# esp32-mementoV3-2021.net
KiCad netlist of a schematic drawn in EAGLE
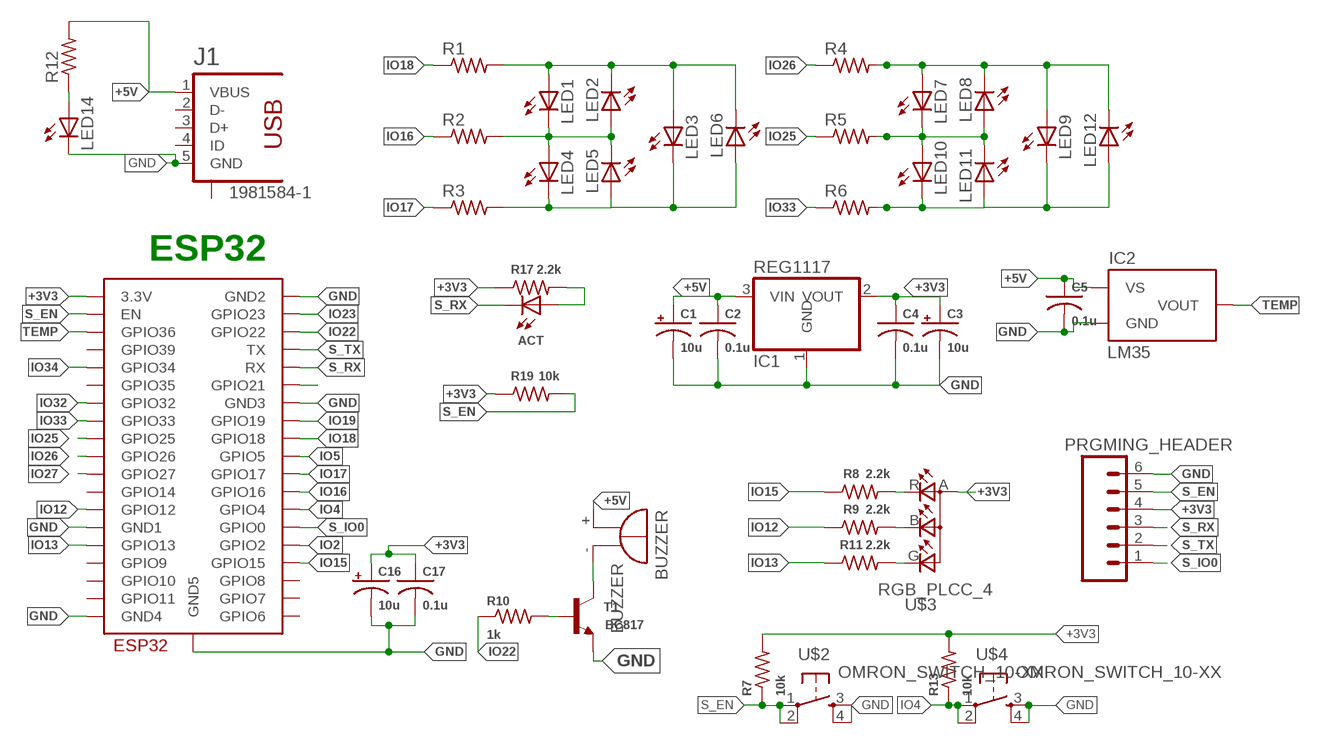
[diagram p0: schematic, sheet 1]

(export (version "E")
  (design (tool "Eeschema 10.0.6"))
  (components
    (comp (ref "ACT")
      (value "LEDCHIPLED_1206")
      (footprint "eagle-import:CHIPLED_1206")
      (libsource (lib "eagle-import") (part "LEDCHIPLED_1206"))
    )
    (comp (ref "BUZZER")
      (value "BUZZER")
      (footprint "eagle-import:F_TMB")
      (libsource (lib "eagle-import") (part "BUZZER"))
    )
    (comp (ref "C1")
      (value "10u")
      (footprint "eagle-import:B_3528-21R")
      (libsource (lib "eagle-import") (part "CAP_POL_16V"))
    )
    (comp (ref "C2")
      (value "0.1u")
      (footprint "eagle-import:C0603")
      (libsource (lib "eagle-import") (part "CAP0603"))
    )
    (comp (ref "C3")
      (value "10u")
      (footprint "eagle-import:B_3528-21R")
      (libsource (lib "eagle-import") (part "CAP_POL_16V"))
    )
    (comp (ref "C4")
      (value "0.1u")
      (footprint "eagle-import:C0603")
      (libsource (lib "eagle-import") (part "CAP0603"))
    )
    (comp (ref "C5")
      (value "0.1u")
      (footprint "eagle-import:C0603")
      (libsource (lib "eagle-import") (part "CAP0603"))
    )
    (comp (ref "C16")
      (value "10u")
      (footprint "eagle-import:B_3528-21R")
      (libsource (lib "eagle-import") (part "CAP_POL_16V"))
    )
    (comp (ref "C17")
      (value "0.1u")
      (footprint "eagle-import:C0603")
      (libsource (lib "eagle-import") (part "CAP0603"))
    )
    (comp (ref "ESP32_MODULE")
      (value "ESP32-WROOM")
      (footprint "eagle-import:ESP32-WROOM")
      (libsource (lib "eagle-import") (part "ESP32-WROOM"))
    )
    (comp (ref "IC1")
      (value "REG1117")
      (footprint "eagle-import:SOT223")
      (libsource (lib "eagle-import") (part "REG1117"))
    )
    (comp (ref "IC2")
      (value "LM35")
      (footprint "eagle-import:TO92")
      (libsource (lib "eagle-import") (part "LM35"))
    )
    (comp (ref "J1")
      (value "1981584-1")
      (footprint "eagle-import:1981584-1")
      (libsource (lib "eagle-import") (part "1981584-1"))
    )
    (comp (ref "LED1")
      (value "LED1206")
      (footprint "eagle-import:CHIPLED_1206")
      (libsource (lib "eagle-import") (part "LED1206"))
    )
    (comp (ref "LED2")
      (value "LED1206")
      (footprint "eagle-import:CHIPLED_1206")
      (libsource (lib "eagle-import") (part "LED1206"))
    )
    (comp (ref "LED3")
      (value "LED1206")
      (footprint "eagle-import:CHIPLED_1206")
      (libsource (lib "eagle-import") (part "LED1206"))
    )
    (comp (ref "LED4")
      (value "LED1206")
      (footprint "eagle-import:CHIPLED_1206")
      (libsource (lib "eagle-import") (part "LED1206"))
    )
    (comp (ref "LED5")
      (value "LED1206")
      (footprint "eagle-import:CHIPLED_1206")
      (libsource (lib "eagle-import") (part "LED1206"))
    )
    (comp (ref "LED6")
      (value "LED1206")
      (footprint "eagle-import:CHIPLED_1206")
      (libsource (lib "eagle-import") (part "LED1206"))
    )
    (comp (ref "LED7")
      (value "LED1206")
      (footprint "eagle-import:CHIPLED_1206")
      (libsource (lib "eagle-import") (part "LED1206"))
    )
    (comp (ref "LED8")
      (value "LED1206")
      (footprint "eagle-import:CHIPLED_1206")
      (libsource (lib "eagle-import") (part "LED1206"))
    )
    (comp (ref "LED9")
      (value "LED1206")
      (footprint "eagle-import:CHIPLED_1206")
      (libsource (lib "eagle-import") (part "LED1206"))
    )
    (comp (ref "LED10")
      (value "LED1206")
      (footprint "eagle-import:CHIPLED_1206")
      (libsource (lib "eagle-import") (part "LED1206"))
    )
    (comp (ref "LED11")
      (value "LED1206")
      (footprint "eagle-import:CHIPLED_1206")
      (libsource (lib "eagle-import") (part "LED1206"))
    )
    (comp (ref "LED12")
      (value "LED1206")
      (footprint "eagle-import:CHIPLED_1206")
      (libsource (lib "eagle-import") (part "LED1206"))
    )
    (comp (ref "LED14")
      (value "LED1206")
      (footprint "eagle-import:CHIPLED_1206")
      (libsource (lib "eagle-import") (part "LED1206"))
    )
    (comp (ref "PRGMING_HEADER")
      (value "M06")
      (footprint "eagle-import:06P")
      (libsource (lib "eagle-import") (part "M06"))
    )
    (comp (ref "R1")
      (value "RESISTOR0805")
      (footprint "eagle-import:R0805")
      (libsource (lib "eagle-import") (part "RESISTOR0805"))
    )
    (comp (ref "R2")
      (value "RESISTOR0805")
      (footprint "eagle-import:R0805")
      (libsource (lib "eagle-import") (part "RESISTOR0805"))
    )
    (comp (ref "R3")
      (value "RESISTOR0805")
      (footprint "eagle-import:R0805")
      (libsource (lib "eagle-import") (part "RESISTOR0805"))
    )
    (comp (ref "R4")
      (value "RESISTOR0805")
      (footprint "eagle-import:R0805")
      (libsource (lib "eagle-import") (part "RESISTOR0805"))
    )
    (comp (ref "R5")
      (value "RESISTOR0805")
      (footprint "eagle-import:R0805")
      (libsource (lib "eagle-import") (part "RESISTOR0805"))
    )
    (comp (ref "R6")
      (value "RESISTOR0805")
      (footprint "eagle-import:R0805")
      (libsource (lib "eagle-import") (part "RESISTOR0805"))
    )
    (comp (ref "R7")
      (value "10k")
      (footprint "eagle-import:M0805")
      (libsource (lib "eagle-import") (part "rcl_334_R-US_M0805"))
    )
    (comp (ref "R8")
      (value "2.2k")
      (footprint "eagle-import:R0805")
      (libsource (lib "eagle-import") (part "R-US_R0805"))
    )
    (comp (ref "R9")
      (value "2.2k")
      (footprint "eagle-import:R0805")
      (libsource (lib "eagle-import") (part "R-US_R0805"))
    )
    (comp (ref "R10")
      (value "1k")
      (footprint "eagle-import:M0805")
      (libsource (lib "eagle-import") (part "rcl_334_R-US_M0805"))
    )
    (comp (ref "R11")
      (value "2.2k")
      (footprint "eagle-import:R0805")
      (libsource (lib "eagle-import") (part "R-US_R0805"))
    )
    (comp (ref "R12")
      (value "RESISTOR0805")
      (footprint "eagle-import:R0805")
      (libsource (lib "eagle-import") (part "RESISTOR0805"))
    )
    (comp (ref "R13")
      (value "10k")
      (footprint "eagle-import:M0805")
      (libsource (lib "eagle-import") (part "rcl_334_R-US_M0805"))
    )
    (comp (ref "R17")
      (value "2.2k")
      (footprint "eagle-import:R0805")
      (libsource (lib "eagle-import") (part "R-US_R0805"))
    )
    (comp (ref "R19")
      (value "10k")
      (footprint "eagle-import:R0805")
      (libsource (lib "eagle-import") (part "R-US_R0805"))
    )
    (comp (ref "T1")
      (value "BC817")
      (footprint "eagle-import:SOT23-BEC")
      (libsource (lib "eagle-import") (part "BC817SMD-40"))
    )
    (comp (ref "U$2")
      (value "OMRON_SWITCH_10-XX")
      (footprint "eagle-import:B3F-10XX")
      (libsource (lib "eagle-import") (part "OMRON_SWITCH_10-XX"))
    )
    (comp (ref "U$3")
      (value "RGB_PLCC_4")
      (footprint "eagle-import:PLCC-4")
      (libsource (lib "eagle-import") (part "RGB_PLCC_4"))
    )
    (comp (ref "U$4")
      (value "OMRON_SWITCH_10-XX")
      (footprint "eagle-import:B3F-10XX")
      (libsource (lib "eagle-import") (part "OMRON_SWITCH_10-XX"))
    )
  )
  (nets
    (net (code "1") (name "+3V3") (class "Default")
      (node (ref "C16") (pin "+") (pinfunction "+_+") (pintype "passive"))
      (node (ref "C17") (pin "1") (pinfunction "1_1") (pintype "passive"))
      (node (ref "C3") (pin "+") (pinfunction "+_+") (pintype "passive"))
      (node (ref "C4") (pin "1") (pinfunction "1_1") (pintype "passive"))
      (node (ref "ESP32_MODULE") (pin "3V3") (pinfunction "3.3V_3V3") (pintype "bidirectional"))
      (node (ref "IC1") (pin "2") (pinfunction "VOUT_2") (pintype "output"))
      (node (ref "PRGMING_HEADER") (pin "4") (pinfunction "4_4") (pintype "passive"))
      (node (ref "R13") (pin "2") (pinfunction "2_2") (pintype "passive"))
      (node (ref "R17") (pin "1") (pinfunction "1_1") (pintype "passive"))
      (node (ref "R19") (pin "1") (pinfunction "1_1") (pintype "passive"))
      (node (ref "R7") (pin "2") (pinfunction "2_2") (pintype "passive"))
      (node (ref "U$3") (pin "A") (pinfunction "A2_A") (pintype "passive"))
    )
    (net (code "2") (name "+5V") (class "Default")
      (node (ref "BUZZER") (pin "+") (pinfunction "+_+") (pintype "passive"))
      (node (ref "C1") (pin "+") (pinfunction "+_+") (pintype "passive"))
      (node (ref "C2") (pin "1") (pinfunction "1_1") (pintype "passive"))
      (node (ref "C5") (pin "1") (pinfunction "1_1") (pintype "passive"))
      (node (ref "IC1") (pin "3") (pinfunction "VIN_3") (pintype "input"))
      (node (ref "IC2") (pin "VS") (pinfunction "VS_VS") (pintype "passive"))
      (node (ref "J1") (pin "1") (pinfunction "VBUS_1") (pintype "passive"))
      (node (ref "R12") (pin "2") (pinfunction "2_2") (pintype "passive"))
    )
    (net (code "3") (name "GND") (class "Default")
      (node (ref "C1") (pin "-") (pinfunction "-_-") (pintype "passive"))
      (node (ref "C16") (pin "-") (pinfunction "-_-") (pintype "passive"))
      (node (ref "C17") (pin "2") (pinfunction "2_2") (pintype "passive"))
      (node (ref "C2") (pin "2") (pinfunction "2_2") (pintype "passive"))
      (node (ref "C3") (pin "-") (pinfunction "-_-") (pintype "passive"))
      (node (ref "C4") (pin "2") (pinfunction "2_2") (pintype "passive"))
      (node (ref "C5") (pin "2") (pinfunction "2_2") (pintype "passive"))
      (node (ref "ESP32_MODULE") (pin "GND1") (pinfunction "GND1_GND1") (pintype "bidirectional"))
      (node (ref "ESP32_MODULE") (pin "GND2") (pinfunction "GND2_GND2") (pintype "bidirectional"))
      (node (ref "ESP32_MODULE") (pin "GND3") (pinfunction "GND3_GND3") (pintype "bidirectional"))
      (node (ref "ESP32_MODULE") (pin "GND4") (pinfunction "GND4_GND4") (pintype "bidirectional"))
      (node (ref "ESP32_MODULE") (pin "GND5") (pinfunction "GND5_GND5") (pintype "bidirectional"))
      (node (ref "IC1") (pin "1") (pinfunction "GND_1") (pintype "power_in"))
      (node (ref "IC2") (pin "GND") (pinfunction "GND_GND") (pintype "passive"))
      (node (ref "J1") (pin "5") (pinfunction "GND_5") (pintype "passive"))
      (node (ref "LED14") (pin "C") (pinfunction "C_C") (pintype "passive"))
      (node (ref "PRGMING_HEADER") (pin "6") (pinfunction "6_6") (pintype "passive"))
      (node (ref "T1") (pin "E") (pinfunction "E_E") (pintype "passive"))
      (node (ref "U$2") (pin "3") (pinfunction "S_3") (pintype "passive"))
      (node (ref "U$2") (pin "4") (pinfunction "S1_4") (pintype "passive"))
      (node (ref "U$4") (pin "3") (pinfunction "S_3") (pintype "passive"))
      (node (ref "U$4") (pin "4") (pinfunction "S1_4") (pintype "passive"))
    )
    (net (code "4") (name "IO2") (class "Default")
      (node (ref "ESP32_MODULE") (pin "IO2") (pinfunction "GPIO2_IO2") (pintype "bidirectional"))
    )
    (net (code "5") (name "IO4") (class "Default")
      (node (ref "ESP32_MODULE") (pin "IO4") (pinfunction "GPIO4_IO4") (pintype "bidirectional"))
      (node (ref "R13") (pin "1") (pinfunction "1_1") (pintype "passive"))
      (node (ref "U$4") (pin "1") (pinfunction "P_1") (pintype "passive"))
      (node (ref "U$4") (pin "2") (pinfunction "P1_2") (pintype "passive"))
    )
    (net (code "6") (name "IO5") (class "Default")
      (node (ref "ESP32_MODULE") (pin "IO5") (pinfunction "GPIO5_IO5") (pintype "bidirectional"))
    )
    (net (code "7") (name "IO12") (class "Default")
      (node (ref "ESP32_MODULE") (pin "IO12") (pinfunction "GPIO12_IO12") (pintype "bidirectional"))
      (node (ref "R9") (pin "1") (pinfunction "1_1") (pintype "passive"))
    )
    (net (code "8") (name "IO13") (class "Default")
      (node (ref "ESP32_MODULE") (pin "IO13") (pinfunction "GPIO13_IO13") (pintype "bidirectional"))
      (node (ref "R11") (pin "1") (pinfunction "1_1") (pintype "passive"))
    )
    (net (code "9") (name "IO15") (class "Default")
      (node (ref "ESP32_MODULE") (pin "IO15") (pinfunction "GPIO15_IO15") (pintype "bidirectional"))
      (node (ref "R8") (pin "1") (pinfunction "1_1") (pintype "passive"))
    )
    (net (code "10") (name "IO16") (class "Default")
      (node (ref "ESP32_MODULE") (pin "IO16") (pinfunction "GPIO16_IO16") (pintype "bidirectional"))
      (node (ref "R2") (pin "1") (pinfunction "1_1") (pintype "passive"))
    )
    (net (code "11") (name "IO17") (class "Default")
      (node (ref "ESP32_MODULE") (pin "IO17") (pinfunction "GPIO17_IO17") (pintype "bidirectional"))
      (node (ref "R3") (pin "1") (pinfunction "1_1") (pintype "passive"))
    )
    (net (code "12") (name "IO18") (class "Default")
      (node (ref "ESP32_MODULE") (pin "IO18") (pinfunction "GPIO18_IO18") (pintype "bidirectional"))
      (node (ref "R1") (pin "1") (pinfunction "1_1") (pintype "passive"))
    )
    (net (code "13") (name "IO19") (class "Default")
      (node (ref "ESP32_MODULE") (pin "IO19") (pinfunction "GPIO19_IO19") (pintype "bidirectional"))
    )
    (net (code "14") (name "IO22") (class "Default")
      (node (ref "ESP32_MODULE") (pin "IO22") (pinfunction "GPIO22_IO22") (pintype "bidirectional"))
      (node (ref "R10") (pin "1") (pinfunction "1_1") (pintype "passive"))
    )
    (net (code "15") (name "IO23") (class "Default")
      (node (ref "ESP32_MODULE") (pin "IO23") (pinfunction "GPIO23_IO23") (pintype "bidirectional"))
    )
    (net (code "16") (name "IO25") (class "Default")
      (node (ref "ESP32_MODULE") (pin "IO25") (pinfunction "GPIO25_IO25") (pintype "bidirectional"))
      (node (ref "R5") (pin "1") (pinfunction "1_1") (pintype "passive"))
    )
    (net (code "17") (name "IO26") (class "Default")
      (node (ref "ESP32_MODULE") (pin "IO26") (pinfunction "GPIO26_IO26") (pintype "bidirectional"))
      (node (ref "R4") (pin "1") (pinfunction "1_1") (pintype "passive"))
    )
    (net (code "18") (name "IO27") (class "Default")
      (node (ref "ESP32_MODULE") (pin "IO27") (pinfunction "GPIO27_IO27") (pintype "bidirectional"))
    )
    (net (code "19") (name "IO32") (class "Default")
      (node (ref "ESP32_MODULE") (pin "IO32") (pinfunction "GPIO32_IO32") (pintype "bidirectional"))
    )
    (net (code "20") (name "IO33") (class "Default")
      (node (ref "ESP32_MODULE") (pin "IO33") (pinfunction "GPIO33_IO33") (pintype "bidirectional"))
      (node (ref "R6") (pin "1") (pinfunction "1_1") (pintype "passive"))
    )
    (net (code "21") (name "IO34") (class "Default")
      (node (ref "ESP32_MODULE") (pin "IO34") (pinfunction "GPIO34_IO34") (pintype "bidirectional"))
    )
    (net (code "22") (name "Net-(ACT-PadA)") (class "Default")
      (node (ref "ACT") (pin "A") (pinfunction "A_A") (pintype "passive"))
      (node (ref "R17") (pin "2") (pinfunction "2_2") (pintype "passive"))
    )
    (net (code "23") (name "Net-(BUZZER-Pad-)") (class "Default")
      (node (ref "BUZZER") (pin "-") (pinfunction "-_-") (pintype "passive"))
      (node (ref "T1") (pin "C") (pinfunction "C_C") (pintype "passive"))
    )
    (net (code "24") (name "Net-(LED1-PadA)") (class "Default")
      (node (ref "LED1") (pin "A") (pinfunction "A_A") (pintype "passive"))
      (node (ref "LED2") (pin "C") (pinfunction "C_C") (pintype "passive"))
      (node (ref "LED3") (pin "A") (pinfunction "A_A") (pintype "passive"))
      (node (ref "LED6") (pin "C") (pinfunction "C_C") (pintype "passive"))
      (node (ref "R1") (pin "2") (pinfunction "2_2") (pintype "passive"))
    )
    (net (code "25") (name "Net-(LED1-PadC)") (class "Default")
      (node (ref "LED1") (pin "C") (pinfunction "C_C") (pintype "passive"))
      (node (ref "LED2") (pin "A") (pinfunction "A_A") (pintype "passive"))
      (node (ref "LED4") (pin "A") (pinfunction "A_A") (pintype "passive"))
      (node (ref "LED5") (pin "C") (pinfunction "C_C") (pintype "passive"))
      (node (ref "R2") (pin "2") (pinfunction "2_2") (pintype "passive"))
    )
    (net (code "26") (name "Net-(LED3-PadC)") (class "Default")
      (node (ref "LED3") (pin "C") (pinfunction "C_C") (pintype "passive"))
      (node (ref "LED4") (pin "C") (pinfunction "C_C") (pintype "passive"))
      (node (ref "LED5") (pin "A") (pinfunction "A_A") (pintype "passive"))
      (node (ref "LED6") (pin "A") (pinfunction "A_A") (pintype "passive"))
      (node (ref "R3") (pin "2") (pinfunction "2_2") (pintype "passive"))
    )
    (net (code "27") (name "Net-(LED10-PadA)") (class "Default")
      (node (ref "LED10") (pin "A") (pinfunction "A_A") (pintype "passive"))
      (node (ref "LED11") (pin "C") (pinfunction "C_C") (pintype "passive"))
      (node (ref "LED7") (pin "C") (pinfunction "C_C") (pintype "passive"))
      (node (ref "LED8") (pin "A") (pinfunction "A_A") (pintype "passive"))
      (node (ref "R5") (pin "2") (pinfunction "2_2") (pintype "passive"))
    )
    (net (code "28") (name "Net-(LED10-PadC)") (class "Default")
      (node (ref "LED10") (pin "C") (pinfunction "C_C") (pintype "passive"))
      (node (ref "LED11") (pin "A") (pinfunction "A_A") (pintype "passive"))
      (node (ref "LED12") (pin "A") (pinfunction "A_A") (pintype "passive"))
      (node (ref "LED9") (pin "C") (pinfunction "C_C") (pintype "passive"))
      (node (ref "R6") (pin "2") (pinfunction "2_2") (pintype "passive"))
    )
    (net (code "29") (name "Net-(LED12-PadC)") (class "Default")
      (node (ref "LED12") (pin "C") (pinfunction "C_C") (pintype "passive"))
      (node (ref "LED7") (pin "A") (pinfunction "A_A") (pintype "passive"))
      (node (ref "LED8") (pin "C") (pinfunction "C_C") (pintype "passive"))
      (node (ref "LED9") (pin "A") (pinfunction "A_A") (pintype "passive"))
      (node (ref "R4") (pin "2") (pinfunction "2_2") (pintype "passive"))
    )
    (net (code "30") (name "Net-(LED14-PadA)") (class "Default")
      (node (ref "LED14") (pin "A") (pinfunction "A_A") (pintype "passive"))
      (node (ref "R12") (pin "1") (pinfunction "1_1") (pintype "passive"))
    )
    (net (code "31") (name "Net-(R10-Pad2)") (class "Default")
      (node (ref "R10") (pin "2") (pinfunction "2_2") (pintype "passive"))
      (node (ref "T1") (pin "B") (pinfunction "B_B") (pintype "passive"))
    )
    (net (code "32") (name "Net-(U$3-CBLUE)") (class "Default")
      (node (ref "R9") (pin "2") (pinfunction "2_2") (pintype "passive"))
      (node (ref "U$3") (pin "B") (pinfunction "CBLUE_B") (pintype "passive"))
    )
    (net (code "33") (name "Net-(U$3-CGREEN)") (class "Default")
      (node (ref "R11") (pin "2") (pinfunction "2_2") (pintype "passive"))
      (node (ref "U$3") (pin "G") (pinfunction "CGREEN_G") (pintype "passive"))
    )
    (net (code "34") (name "Net-(U$3-CRED)") (class "Default")
      (node (ref "R8") (pin "2") (pinfunction "2_2") (pintype "passive"))
      (node (ref "U$3") (pin "R") (pinfunction "CRED_R") (pintype "passive"))
    )
    (net (code "35") (name "S_EN") (class "Default")
      (node (ref "ESP32_MODULE") (pin "EN") (pinfunction "EN_EN") (pintype "bidirectional"))
      (node (ref "PRGMING_HEADER") (pin "5") (pinfunction "5_5") (pintype "passive"))
      (node (ref "R19") (pin "2") (pinfunction "2_2") (pintype "passive"))
      (node (ref "R7") (pin "1") (pinfunction "1_1") (pintype "passive"))
      (node (ref "U$2") (pin "1") (pinfunction "P_1") (pintype "passive"))
      (node (ref "U$2") (pin "2") (pinfunction "P1_2") (pintype "passive"))
    )
    (net (code "36") (name "S_IO0") (class "Default")
      (node (ref "ESP32_MODULE") (pin "IO0") (pinfunction "GPIO0_IO0") (pintype "bidirectional"))
      (node (ref "PRGMING_HEADER") (pin "1") (pinfunction "1_1") (pintype "passive"))
    )
    (net (code "37") (name "S_RX") (class "Default")
      (node (ref "ACT") (pin "C") (pinfunction "C_C") (pintype "passive"))
      (node (ref "ESP32_MODULE") (pin "RX") (pinfunction "RX_RX") (pintype "bidirectional"))
      (node (ref "PRGMING_HEADER") (pin "3") (pinfunction "3_3") (pintype "passive"))
    )
    (net (code "38") (name "S_TX") (class "Default")
      (node (ref "ESP32_MODULE") (pin "TX") (pinfunction "TX_TX") (pintype "bidirectional"))
      (node (ref "PRGMING_HEADER") (pin "2") (pinfunction "2_2") (pintype "passive"))
    )
    (net (code "39") (name "TEMP") (class "Default")
      (node (ref "ESP32_MODULE") (pin "SENSOR_VP") (pinfunction "GPIO36_SENSOR_VP") (pintype "bidirectional"))
      (node (ref "IC2") (pin "VOUT") (pinfunction "VOUT_VOUT") (pintype "passive"))
    )
    (net (code "40") (name "unconnected-(ESP32_MODULE-GPIO6-PadCLK)") (class "Default")
      (node (ref "ESP32_MODULE") (pin "CLK") (pinfunction "GPIO6_CLK") (pintype "bidirectional"))
    )
    (net (code "41") (name "unconnected-(ESP32_MODULE-GPIO7-PadSD0)") (class "Default")
      (node (ref "ESP32_MODULE") (pin "SD0") (pinfunction "GPIO7_SD0") (pintype "bidirectional"))
    )
    (net (code "42") (name "unconnected-(ESP32_MODULE-GPIO8-PadSD1)") (class "Default")
      (node (ref "ESP32_MODULE") (pin "SD1") (pinfunction "GPIO8_SD1") (pintype "bidirectional"))
    )
    (net (code "43") (name "unconnected-(ESP32_MODULE-GPIO9-PadSD2)") (class "Default")
      (node (ref "ESP32_MODULE") (pin "SD2") (pinfunction "GPIO9_SD2") (pintype "bidirectional"))
    )
    (net (code "44") (name "unconnected-(ESP32_MODULE-GPIO10-PadSD3)") (class "Default")
      (node (ref "ESP32_MODULE") (pin "SD3") (pinfunction "GPIO10_SD3") (pintype "bidirectional"))
    )
    (net (code "45") (name "unconnected-(ESP32_MODULE-GPIO11-PadCMD)") (class "Default")
      (node (ref "ESP32_MODULE") (pin "CMD") (pinfunction "GPIO11_CMD") (pintype "bidirectional"))
    )
    (net (code "46") (name "unconnected-(ESP32_MODULE-GPIO14-PadIO14)") (class "Default")
      (node (ref "ESP32_MODULE") (pin "IO14") (pinfunction "GPIO14_IO14") (pintype "bidirectional"))
    )
    (net (code "47") (name "unconnected-(ESP32_MODULE-GPIO21-PadIO21)") (class "Default")
      (node (ref "ESP32_MODULE") (pin "IO21") (pinfunction "GPIO21_IO21") (pintype "bidirectional"))
    )
    (net (code "48") (name "unconnected-(ESP32_MODULE-GPIO35-PadIO35)") (class "Default")
      (node (ref "ESP32_MODULE") (pin "IO35") (pinfunction "GPIO35_IO35") (pintype "bidirectional"))
    )
    (net (code "49") (name "unconnected-(ESP32_MODULE-GPIO39-PadSENSOR_VN)") (class "Default")
      (node (ref "ESP32_MODULE") (pin "SENSOR_VN") (pinfunction "GPIO39_SENSOR_VN") (pintype "bidirectional"))
    )
    (net (code "50") (name "unconnected-(J1-D+-Pad3)") (class "Default")
      (node (ref "J1") (pin "3") (pinfunction "D+_3") (pintype "passive"))
    )
    (net (code "51") (name "unconnected-(J1-D--Pad2)") (class "Default")
      (node (ref "J1") (pin "2") (pinfunction "D-_2") (pintype "passive"))
    )
    (net (code "52") (name "unconnected-(J1-ID-Pad4)") (class "Default")
      (node (ref "J1") (pin "4") (pinfunction "ID_4") (pintype "passive"))
    )
    (net (code "53") (name "unconnected-(J1-PadS1)") (class "Default")
      (node (ref "J1") (pin "S1") (pinfunction "S1_S1") (pintype "passive"))
    )
  )
)
